# PCB-dol.net
KiCad netlist of a schematic drawn in EAGLE
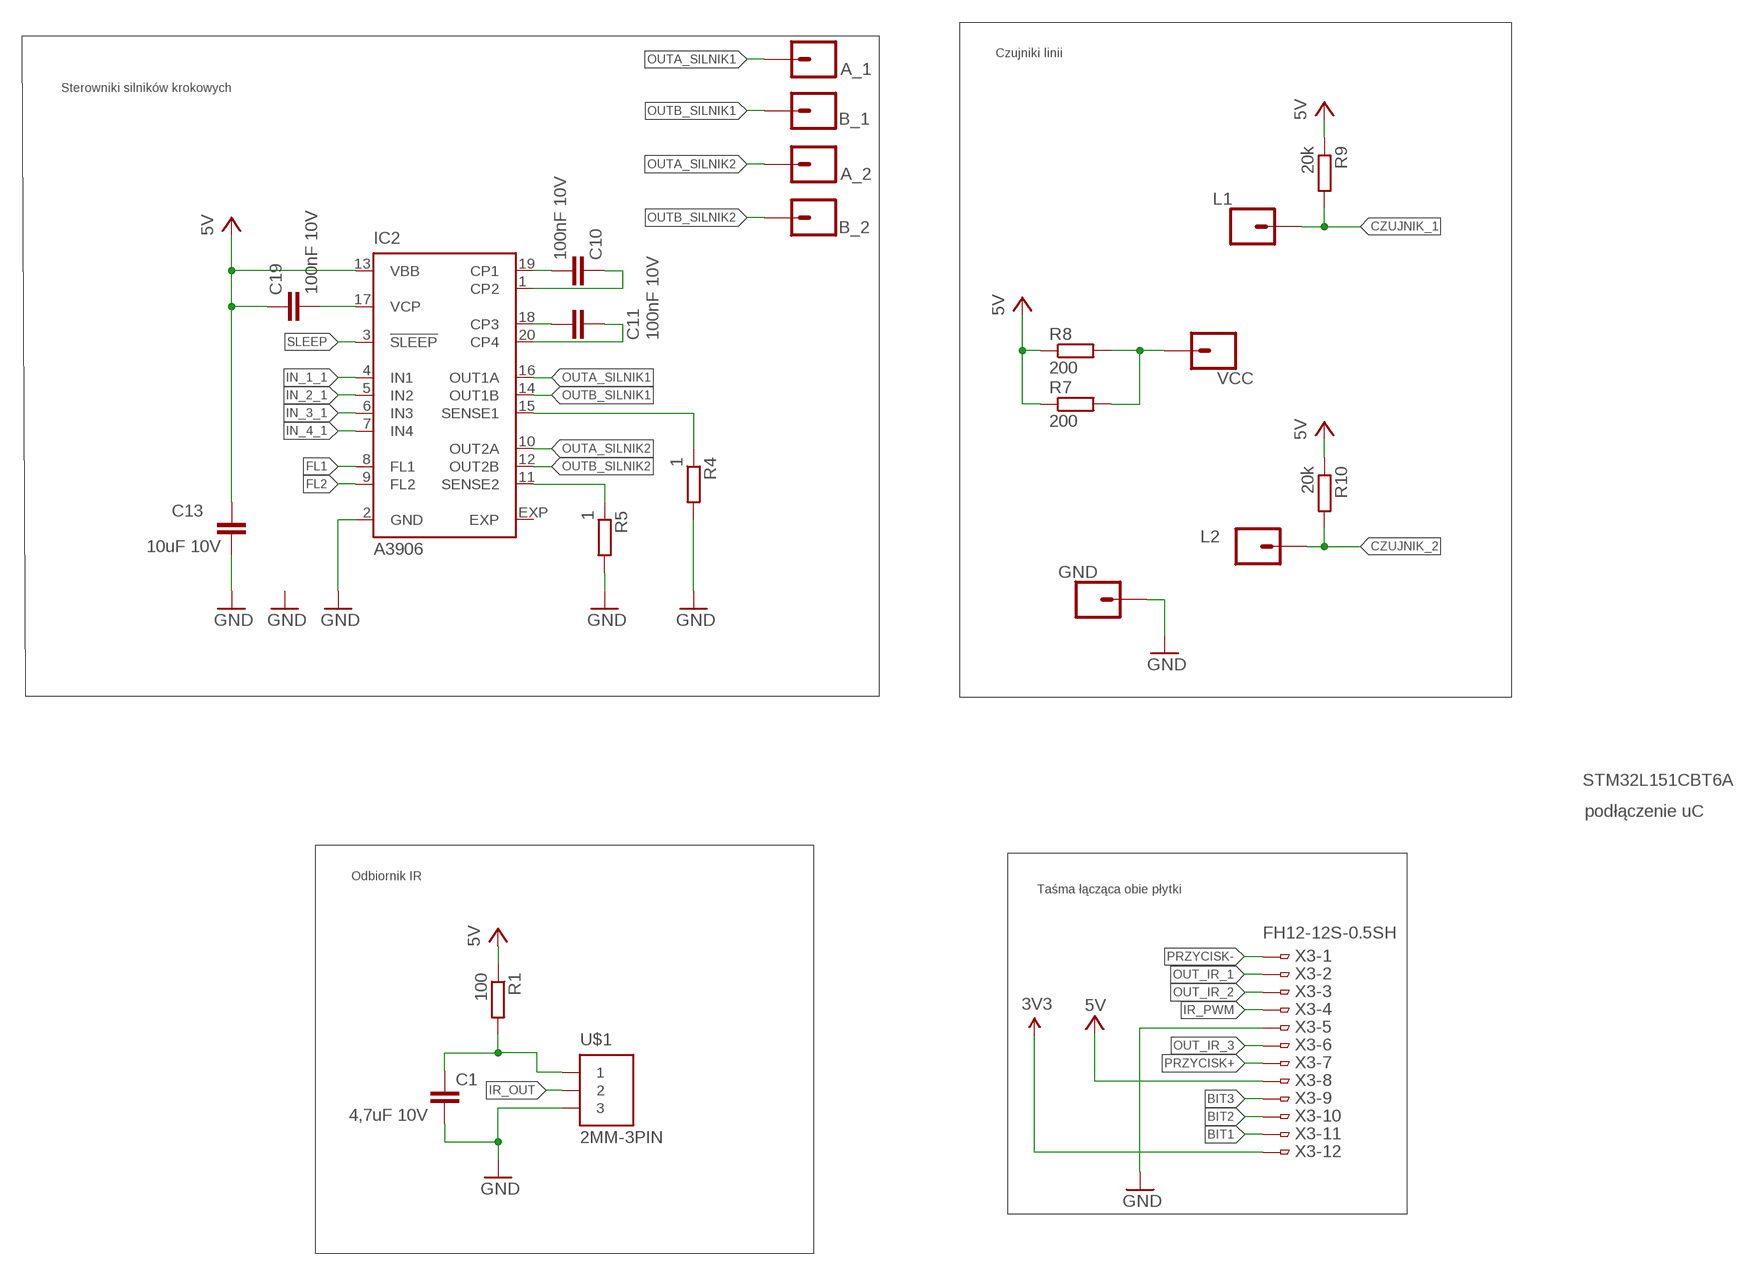
[diagram p0: schematic, sheet 1, part 1 of 2]
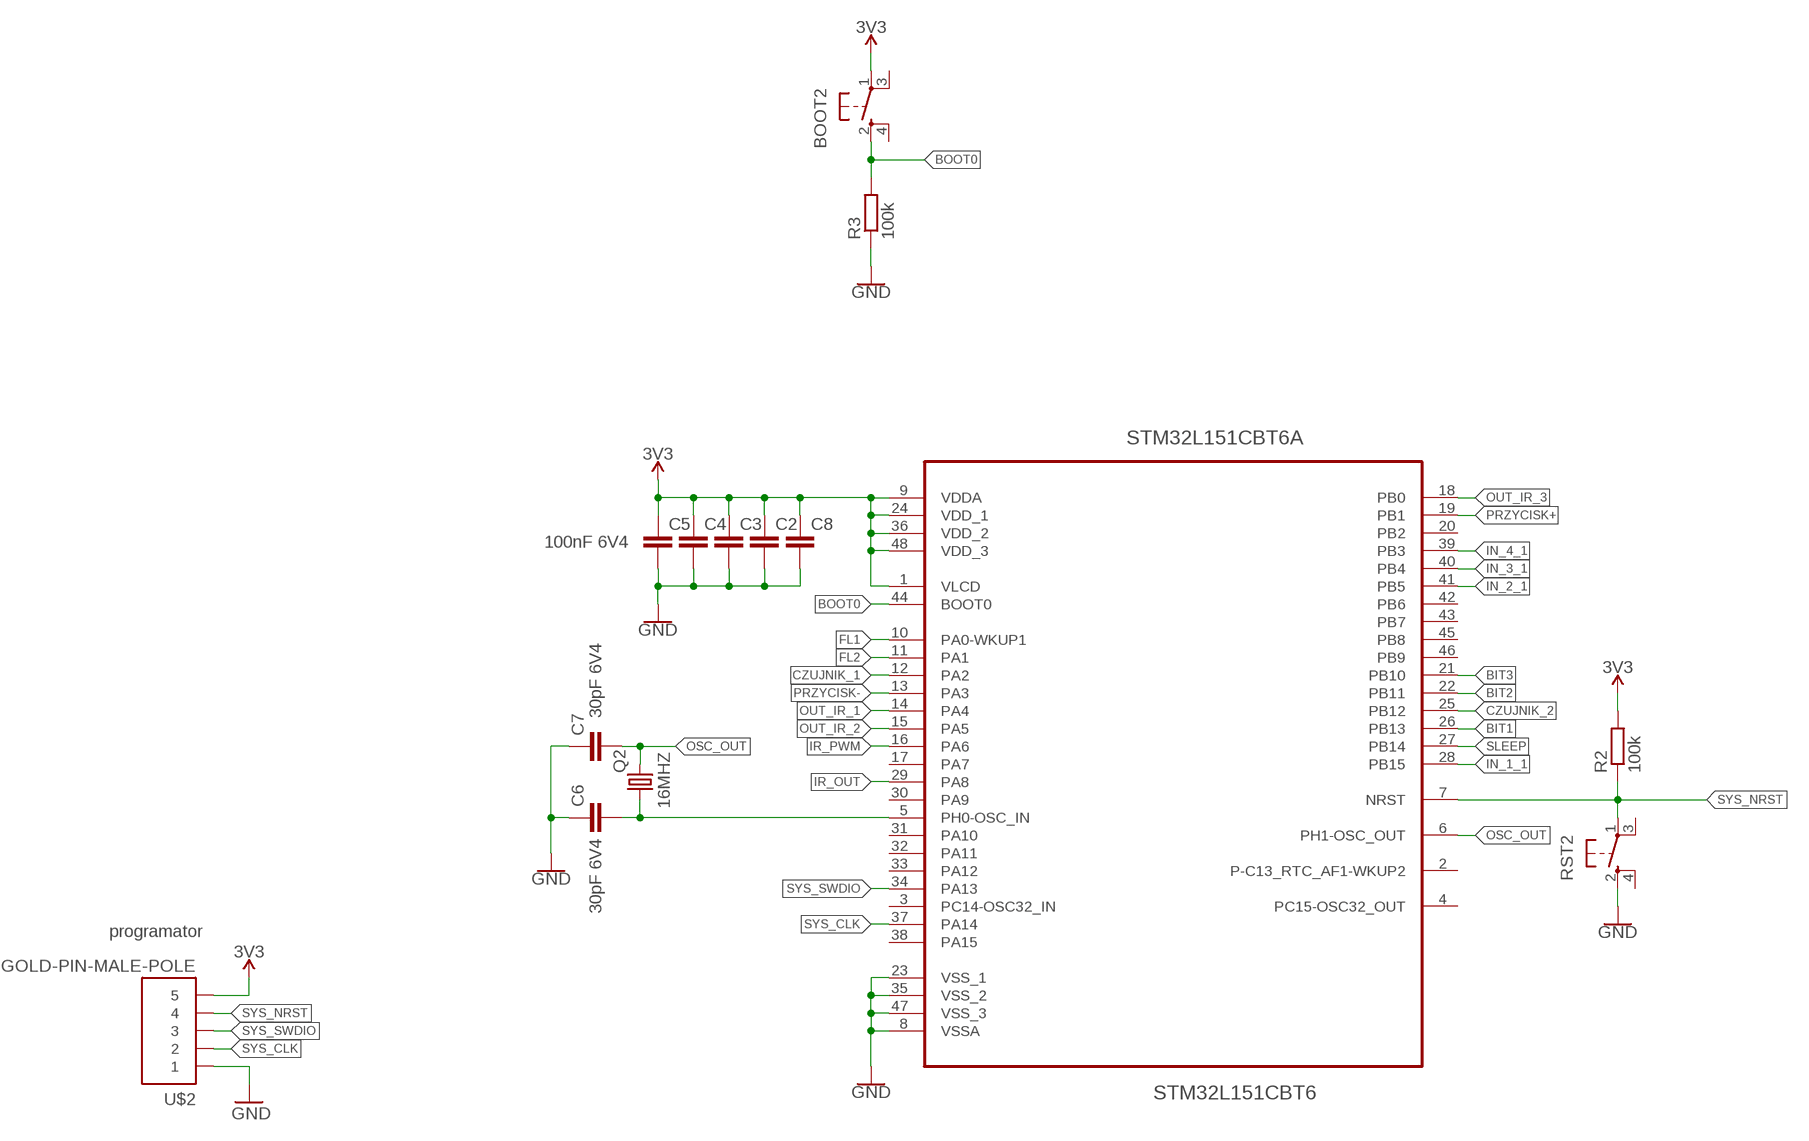
[diagram p1: schematic, sheet 1, part 2 of 2]

(export (version "E")
  (design (tool "Eeschema 10.0.6"))
  (components
    (comp (ref "A_1")
      (value "CONN_01PTH_NO_SILK_KIT")
      (footprint "eagle-import:1X01NS_KIT")
      (libsource (lib "eagle-import") (part "CONN_01PTH_NO_SILK_KIT"))
    )
    (comp (ref "A_2")
      (value "CONN_01PTH_NO_SILK_KIT")
      (footprint "eagle-import:1X01NS_KIT")
      (libsource (lib "eagle-import") (part "CONN_01PTH_NO_SILK_KIT"))
    )
    (comp (ref "BOOT2")
      (value "SPST_TACT-KMR2")
      (footprint "eagle-import:KMR2")
      (libsource (lib "eagle-import") (part "SPST_TACT-KMR2"))
    )
    (comp (ref "B_1")
      (value "CONN_01PTH_NO_SILK_KIT")
      (footprint "eagle-import:1X01NS_KIT")
      (libsource (lib "eagle-import") (part "CONN_01PTH_NO_SILK_KIT"))
    )
    (comp (ref "B_2")
      (value "CONN_01PTH_NO_SILK_KIT")
      (footprint "eagle-import:1X01NS_KIT")
      (libsource (lib "eagle-import") (part "CONN_01PTH_NO_SILK_KIT"))
    )
    (comp (ref "C1")
      (value "4,7uF 10V")
      (footprint "eagle-import:C0402")
      (libsource (lib "eagle-import") (part "C-EUC0402"))
    )
    (comp (ref "C2")
      (value "100nF 6V4")
      (footprint "eagle-import:C0402")
      (libsource (lib "eagle-import") (part "C-EUC0402"))
    )
    (comp (ref "C3")
      (value "100nF 6V4")
      (footprint "eagle-import:C0402")
      (libsource (lib "eagle-import") (part "C-EUC0402"))
    )
    (comp (ref "C4")
      (value "100nF 6V4")
      (footprint "eagle-import:C0402")
      (libsource (lib "eagle-import") (part "C-EUC0402"))
    )
    (comp (ref "C5")
      (value "100nF 6V4")
      (footprint "eagle-import:C0402")
      (libsource (lib "eagle-import") (part "C-EUC0402"))
    )
    (comp (ref "C6")
      (value "30pF 6V4")
      (footprint "eagle-import:C0402")
      (libsource (lib "eagle-import") (part "C-EUC0402"))
    )
    (comp (ref "C7")
      (value "30pF 6V4")
      (footprint "eagle-import:C0402")
      (libsource (lib "eagle-import") (part "C-EUC0402"))
    )
    (comp (ref "C8")
      (value "100nF 6V4")
      (footprint "eagle-import:C0402")
      (libsource (lib "eagle-import") (part "C-EUC0402"))
    )
    (comp (ref "C10")
      (value "100nF 10V")
      (footprint "eagle-import:C0402")
      (libsource (lib "eagle-import") (part "C-EUC0402"))
    )
    (comp (ref "C11")
      (value "100nF 10V")
      (footprint "eagle-import:C0402")
      (libsource (lib "eagle-import") (part "C-EUC0402"))
    )
    (comp (ref "C13")
      (value "10uF 10V")
      (footprint "eagle-import:C0402")
      (libsource (lib "eagle-import") (part "C-EUC0402"))
    )
    (comp (ref "C19")
      (value "100nF 10V")
      (footprint "eagle-import:C0402")
      (libsource (lib "eagle-import") (part "C-EUC0402"))
    )
    (comp (ref "GND")
      (value "CONN_01PTH_NO_SILK_KIT")
      (footprint "eagle-import:1X01NS_KIT")
      (libsource (lib "eagle-import") (part "CONN_01PTH_NO_SILK_KIT"))
    )
    (comp (ref "IC2")
      (value "A3906")
      (footprint "eagle-import:QFN20")
      (libsource (lib "eagle-import") (part "A3906"))
    )
    (comp (ref "L1")
      (value "CONN_01PTH_NO_SILK_KIT")
      (footprint "eagle-import:1X01NS_KIT")
      (libsource (lib "eagle-import") (part "CONN_01PTH_NO_SILK_KIT"))
    )
    (comp (ref "L2")
      (value "CONN_01PTH_NO_SILK_KIT")
      (footprint "eagle-import:1X01NS_KIT")
      (libsource (lib "eagle-import") (part "CONN_01PTH_NO_SILK_KIT"))
    )
    (comp (ref "Q2")
      (value "16MHZ")
      (footprint "eagle-import:3.2X2.5_KX-7")
      (libsource (lib "eagle-import") (part "KX-7"))
    )
    (comp (ref "R1")
      (value "100")
      (footprint "eagle-import:R0402")
      (libsource (lib "eagle-import") (part "R-EU_R0402"))
    )
    (comp (ref "R2")
      (value "100k")
      (footprint "eagle-import:R0402")
      (libsource (lib "eagle-import") (part "R-EU_R0402"))
    )
    (comp (ref "R3")
      (value "100k")
      (footprint "eagle-import:R0402")
      (libsource (lib "eagle-import") (part "R-EU_R0402"))
    )
    (comp (ref "R4")
      (value "1")
      (footprint "eagle-import:R0402")
      (libsource (lib "eagle-import") (part "R-EU_R0402"))
    )
    (comp (ref "R5")
      (value "1")
      (footprint "eagle-import:R0402")
      (libsource (lib "eagle-import") (part "R-EU_R0402"))
    )
    (comp (ref "R7")
      (value "200")
      (footprint "eagle-import:R0805")
      (libsource (lib "eagle-import") (part "R-EU_R0805"))
    )
    (comp (ref "R8")
      (value "200")
      (footprint "eagle-import:R0805")
      (libsource (lib "eagle-import") (part "R-EU_R0805"))
    )
    (comp (ref "R9")
      (value "20k")
      (footprint "eagle-import:R0402")
      (libsource (lib "eagle-import") (part "R-EU_R0402"))
    )
    (comp (ref "R10")
      (value "20k")
      (footprint "eagle-import:R0402")
      (libsource (lib "eagle-import") (part "R-EU_R0402"))
    )
    (comp (ref "RST2")
      (value "SPST_TACT-KMR2")
      (footprint "eagle-import:KMR2")
      (libsource (lib "eagle-import") (part "SPST_TACT-KMR2"))
    )
    (comp (ref "STM32L151CBT6A")
      (value "STM32L151CBT6")
      (footprint "eagle-import:QFP50P900X900X160-48N")
      (libsource (lib "eagle-import") (part "STM32L151CBT6"))
    )
    (comp (ref "U$1")
      (value "2MM-3PIN")
      (footprint "eagle-import:2MM-3PIN")
      (libsource (lib "eagle-import") (part "2MM-3PIN"))
    )
    (comp (ref "U$2")
      (value "GOLD-PIN-MALE-POLE")
      (footprint "eagle-import:PIN5")
      (libsource (lib "eagle-import") (part "GOLD-PIN-MALE-POLE"))
    )
    (comp (ref "VCC")
      (value "CONN_01PTH_NO_SILK_KIT")
      (footprint "eagle-import:1X01NS_KIT")
      (libsource (lib "eagle-import") (part "CONN_01PTH_NO_SILK_KIT"))
    )
    (comp (ref "X3")
      (value "FH12-12S-0.5SH")
      (footprint "eagle-import:FH12-12S-0.5SH")
      (fields (field (name "MPN") "FH12-12S-0.5SH(55)"))
      (libsource (lib "eagle-import") (part "FH12-12S-0.5SH"))
    )
  )
  (nets
    (net (code "1") (name "3V3") (class "Default")
      (node (ref "BOOT2") (pin "1") (pinfunction "P_1") (pintype "passive"))
      (node (ref "C2") (pin "1") (pinfunction "1_1") (pintype "passive"))
      (node (ref "C3") (pin "1") (pinfunction "1_1") (pintype "passive"))
      (node (ref "C4") (pin "1") (pinfunction "1_1") (pintype "passive"))
      (node (ref "C5") (pin "1") (pinfunction "1_1") (pintype "passive"))
      (node (ref "C8") (pin "1") (pinfunction "1_1") (pintype "passive"))
      (node (ref "R2") (pin "2") (pinfunction "2_2") (pintype "passive"))
      (node (ref "STM32L151CBT6A") (pin "1") (pinfunction "VLCD_1") (pintype "power_in"))
      (node (ref "STM32L151CBT6A") (pin "24") (pinfunction "VDD_1_24") (pintype "power_in"))
      (node (ref "STM32L151CBT6A") (pin "36") (pinfunction "VDD_2_36") (pintype "power_in"))
      (node (ref "STM32L151CBT6A") (pin "48") (pinfunction "VDD_3_48") (pintype "power_in"))
      (node (ref "STM32L151CBT6A") (pin "9") (pinfunction "VDDA_9") (pintype "power_in"))
      (node (ref "U$2") (pin "P$5") (pinfunction "5_P$5") (pintype "input"))
      (node (ref "X3") (pin "12") (pinfunction "1_12") (pintype "passive"))
    )
    (net (code "2") (name "5V") (class "Default")
      (node (ref "C13") (pin "2") (pinfunction "2_2") (pintype "passive"))
      (node (ref "C19") (pin "2") (pinfunction "2_2") (pintype "passive"))
      (node (ref "IC2") (pin "13") (pinfunction "VBB_13") (pintype "power_in"))
      (node (ref "R1") (pin "1") (pinfunction "1_1") (pintype "passive"))
      (node (ref "R10") (pin "1") (pinfunction "1_1") (pintype "passive"))
      (node (ref "R7") (pin "1") (pinfunction "1_1") (pintype "passive"))
      (node (ref "R8") (pin "1") (pinfunction "1_1") (pintype "passive"))
      (node (ref "R9") (pin "1") (pinfunction "1_1") (pintype "passive"))
      (node (ref "X3") (pin "8") (pinfunction "1_8") (pintype "passive"))
    )
    (net (code "3") (name "BIT1") (class "Default")
      (node (ref "STM32L151CBT6A") (pin "26") (pinfunction "PB13_26") (pintype "bidirectional"))
      (node (ref "X3") (pin "11") (pinfunction "1_11") (pintype "passive"))
    )
    (net (code "4") (name "BIT2") (class "Default")
      (node (ref "STM32L151CBT6A") (pin "22") (pinfunction "PB11_22") (pintype "bidirectional"))
      (node (ref "X3") (pin "10") (pinfunction "1_10") (pintype "passive"))
    )
    (net (code "5") (name "BIT3") (class "Default")
      (node (ref "STM32L151CBT6A") (pin "21") (pinfunction "PB10_21") (pintype "bidirectional"))
      (node (ref "X3") (pin "9") (pinfunction "1_9") (pintype "passive"))
    )
    (net (code "6") (name "BOOT0") (class "Default")
      (node (ref "BOOT2") (pin "2") (pinfunction "S_2") (pintype "passive"))
      (node (ref "R3") (pin "2") (pinfunction "2_2") (pintype "passive"))
      (node (ref "STM32L151CBT6A") (pin "44") (pinfunction "BOOT0_44") (pintype "input"))
    )
    (net (code "7") (name "CZUJNIK_1") (class "Default")
      (node (ref "L1") (pin "1") (pinfunction "1_1") (pintype "passive"))
      (node (ref "R9") (pin "2") (pinfunction "2_2") (pintype "passive"))
      (node (ref "STM32L151CBT6A") (pin "12") (pinfunction "PA2_12") (pintype "bidirectional"))
    )
    (net (code "8") (name "CZUJNIK_2") (class "Default")
      (node (ref "L2") (pin "1") (pinfunction "1_1") (pintype "passive"))
      (node (ref "R10") (pin "2") (pinfunction "2_2") (pintype "passive"))
      (node (ref "STM32L151CBT6A") (pin "25") (pinfunction "PB12_25") (pintype "bidirectional"))
    )
    (net (code "9") (name "FL1") (class "Default")
      (node (ref "IC2") (pin "8") (pinfunction "FL1_8") (pintype "input"))
      (node (ref "STM32L151CBT6A") (pin "10") (pinfunction "PA0-WKUP1_10") (pintype "bidirectional"))
    )
    (net (code "10") (name "FL2") (class "Default")
      (node (ref "IC2") (pin "9") (pinfunction "FL2_9") (pintype "input"))
      (node (ref "STM32L151CBT6A") (pin "11") (pinfunction "PA1_11") (pintype "bidirectional"))
    )
    (net (code "11") (name "GND") (class "Default")
      (node (ref "C1") (pin "2") (pinfunction "2_2") (pintype "passive"))
      (node (ref "C13") (pin "1") (pinfunction "1_1") (pintype "passive"))
      (node (ref "C2") (pin "2") (pinfunction "2_2") (pintype "passive"))
      (node (ref "C3") (pin "2") (pinfunction "2_2") (pintype "passive"))
      (node (ref "C4") (pin "2") (pinfunction "2_2") (pintype "passive"))
      (node (ref "C5") (pin "2") (pinfunction "2_2") (pintype "passive"))
      (node (ref "C6") (pin "1") (pinfunction "1_1") (pintype "passive"))
      (node (ref "C7") (pin "1") (pinfunction "1_1") (pintype "passive"))
      (node (ref "C8") (pin "2") (pinfunction "2_2") (pintype "passive"))
      (node (ref "GND") (pin "1") (pinfunction "1_1") (pintype "passive"))
      (node (ref "IC2") (pin "2") (pinfunction "GND_2") (pintype "power_in"))
      (node (ref "R3") (pin "1") (pinfunction "1_1") (pintype "passive"))
      (node (ref "R4") (pin "2") (pinfunction "2_2") (pintype "passive"))
      (node (ref "R5") (pin "2") (pinfunction "2_2") (pintype "passive"))
      (node (ref "RST2") (pin "2") (pinfunction "S_2") (pintype "passive"))
      (node (ref "STM32L151CBT6A") (pin "23") (pinfunction "VSS_1_23") (pintype "power_in"))
      (node (ref "STM32L151CBT6A") (pin "35") (pinfunction "VSS_2_35") (pintype "power_in"))
      (node (ref "STM32L151CBT6A") (pin "47") (pinfunction "VSS_3_47") (pintype "power_in"))
      (node (ref "STM32L151CBT6A") (pin "8") (pinfunction "VSSA_8") (pintype "power_in"))
      (node (ref "U$1") (pin "P$3") (pinfunction "3_P$3") (pintype "input"))
      (node (ref "U$2") (pin "P$1") (pinfunction "1_P$1") (pintype "input"))
      (node (ref "X3") (pin "5") (pinfunction "1_5") (pintype "passive"))
    )
    (net (code "12") (name "IN_1_1") (class "Default")
      (node (ref "IC2") (pin "4") (pinfunction "IN1_4") (pintype "input"))
      (node (ref "STM32L151CBT6A") (pin "28") (pinfunction "PB15_28") (pintype "bidirectional"))
    )
    (net (code "13") (name "IN_2_1") (class "Default")
      (node (ref "IC2") (pin "5") (pinfunction "IN2_5") (pintype "input"))
      (node (ref "STM32L151CBT6A") (pin "41") (pinfunction "PB5_41") (pintype "bidirectional"))
    )
    (net (code "14") (name "IN_3_1") (class "Default")
      (node (ref "IC2") (pin "6") (pinfunction "IN3_6") (pintype "input"))
      (node (ref "STM32L151CBT6A") (pin "40") (pinfunction "PB4_40") (pintype "bidirectional"))
    )
    (net (code "15") (name "IN_4_1") (class "Default")
      (node (ref "IC2") (pin "7") (pinfunction "IN4_7") (pintype "input"))
      (node (ref "STM32L151CBT6A") (pin "39") (pinfunction "PB3_39") (pintype "bidirectional"))
    )
    (net (code "16") (name "IR_OUT") (class "Default")
      (node (ref "STM32L151CBT6A") (pin "29") (pinfunction "PA8_29") (pintype "bidirectional"))
      (node (ref "U$1") (pin "P$2") (pinfunction "2_P$2") (pintype "input"))
    )
    (net (code "17") (name "IR_PWM") (class "Default")
      (node (ref "STM32L151CBT6A") (pin "16") (pinfunction "PA6_16") (pintype "bidirectional"))
      (node (ref "X3") (pin "4") (pinfunction "1_4") (pintype "passive"))
    )
    (net (code "18") (name "Net-(IC2-CP1)") (class "Default")
      (node (ref "C10") (pin "1") (pinfunction "1_1") (pintype "passive"))
      (node (ref "IC2") (pin "19") (pinfunction "CP1_19") (pintype "passive"))
    )
    (net (code "19") (name "Net-(IC2-CP2)") (class "Default")
      (node (ref "C10") (pin "2") (pinfunction "2_2") (pintype "passive"))
      (node (ref "IC2") (pin "1") (pinfunction "CP2_1") (pintype "passive"))
    )
    (net (code "20") (name "Net-(IC2-CP3)") (class "Default")
      (node (ref "C11") (pin "1") (pinfunction "1_1") (pintype "passive"))
      (node (ref "IC2") (pin "18") (pinfunction "CP3_18") (pintype "passive"))
    )
    (net (code "21") (name "Net-(IC2-CP4)") (class "Default")
      (node (ref "C11") (pin "2") (pinfunction "2_2") (pintype "passive"))
      (node (ref "IC2") (pin "20") (pinfunction "CP4_20") (pintype "passive"))
    )
    (net (code "22") (name "Net-(IC2-SENSE1)") (class "Default")
      (node (ref "IC2") (pin "15") (pinfunction "SENSE1_15") (pintype "input"))
      (node (ref "R4") (pin "1") (pinfunction "1_1") (pintype "passive"))
    )
    (net (code "23") (name "Net-(IC2-SENSE2)") (class "Default")
      (node (ref "IC2") (pin "11") (pinfunction "SENSE2_11") (pintype "input"))
      (node (ref "R5") (pin "1") (pinfunction "1_1") (pintype "passive"))
    )
    (net (code "24") (name "Net-(IC2-VCP)") (class "Default")
      (node (ref "C19") (pin "1") (pinfunction "1_1") (pintype "passive"))
      (node (ref "IC2") (pin "17") (pinfunction "VCP_17") (pintype "passive"))
    )
    (net (code "25") (name "Net-(R7-Pad2)") (class "Default")
      (node (ref "R7") (pin "2") (pinfunction "2_2") (pintype "passive"))
      (node (ref "R8") (pin "2") (pinfunction "2_2") (pintype "passive"))
      (node (ref "VCC") (pin "1") (pinfunction "1_1") (pintype "passive"))
    )
    (net (code "26") (name "Net-(STM32L151CBT6A-PH0-OSC_IN)") (class "Default")
      (node (ref "C6") (pin "2") (pinfunction "2_2") (pintype "passive"))
      (node (ref "Q2") (pin "1") (pinfunction "1_1") (pintype "passive"))
      (node (ref "STM32L151CBT6A") (pin "5") (pinfunction "PH0-OSC_IN_5") (pintype "input"))
    )
    (net (code "27") (name "Net-(U$1-1)") (class "Default")
      (node (ref "C1") (pin "1") (pinfunction "1_1") (pintype "passive"))
      (node (ref "R1") (pin "2") (pinfunction "2_2") (pintype "passive"))
      (node (ref "U$1") (pin "P$1") (pinfunction "1_P$1") (pintype "input"))
    )
    (net (code "28") (name "OSC_OUT") (class "Default")
      (node (ref "C7") (pin "2") (pinfunction "2_2") (pintype "passive"))
      (node (ref "Q2") (pin "3") (pinfunction "2_3") (pintype "passive"))
      (node (ref "STM32L151CBT6A") (pin "6") (pinfunction "PH1-OSC_OUT_6") (pintype "output"))
    )
    (net (code "29") (name "OUTA_SILNIK1") (class "Default")
      (node (ref "A_1") (pin "1") (pinfunction "1_1") (pintype "passive"))
      (node (ref "IC2") (pin "16") (pinfunction "OUT1A_16") (pintype "output"))
    )
    (net (code "30") (name "OUTA_SILNIK2") (class "Default")
      (node (ref "A_2") (pin "1") (pinfunction "1_1") (pintype "passive"))
      (node (ref "IC2") (pin "10") (pinfunction "OUT2A_10") (pintype "output"))
    )
    (net (code "31") (name "OUTB_SILNIK1") (class "Default")
      (node (ref "B_1") (pin "1") (pinfunction "1_1") (pintype "passive"))
      (node (ref "IC2") (pin "14") (pinfunction "OUT1B_14") (pintype "output"))
    )
    (net (code "32") (name "OUTB_SILNIK2") (class "Default")
      (node (ref "B_2") (pin "1") (pinfunction "1_1") (pintype "passive"))
      (node (ref "IC2") (pin "12") (pinfunction "OUT2B_12") (pintype "output"))
    )
    (net (code "33") (name "OUT_IR_1") (class "Default")
      (node (ref "STM32L151CBT6A") (pin "14") (pinfunction "PA4_14") (pintype "bidirectional"))
      (node (ref "X3") (pin "2") (pinfunction "1_2") (pintype "passive"))
    )
    (net (code "34") (name "OUT_IR_2") (class "Default")
      (node (ref "STM32L151CBT6A") (pin "15") (pinfunction "PA5_15") (pintype "bidirectional"))
      (node (ref "X3") (pin "3") (pinfunction "1_3") (pintype "passive"))
    )
    (net (code "35") (name "OUT_IR_3") (class "Default")
      (node (ref "STM32L151CBT6A") (pin "18") (pinfunction "PB0_18") (pintype "bidirectional"))
      (node (ref "X3") (pin "6") (pinfunction "1_6") (pintype "passive"))
    )
    (net (code "36") (name "PRZYCISK+") (class "Default")
      (node (ref "STM32L151CBT6A") (pin "19") (pinfunction "PB1_19") (pintype "bidirectional"))
      (node (ref "X3") (pin "7") (pinfunction "1_7") (pintype "passive"))
    )
    (net (code "37") (name "PRZYCISK-") (class "Default")
      (node (ref "STM32L151CBT6A") (pin "13") (pinfunction "PA3_13") (pintype "bidirectional"))
      (node (ref "X3") (pin "1") (pinfunction "1_1") (pintype "passive"))
    )
    (net (code "38") (name "SLEEP") (class "Default")
      (node (ref "IC2") (pin "3") (pinfunction "~{SLEEP}_3") (pintype "input"))
      (node (ref "STM32L151CBT6A") (pin "27") (pinfunction "PB14_27") (pintype "bidirectional"))
    )
    (net (code "39") (name "SYS_CLK") (class "Default")
      (node (ref "STM32L151CBT6A") (pin "37") (pinfunction "PA14_37") (pintype "bidirectional"))
      (node (ref "U$2") (pin "P$2") (pinfunction "2_P$2") (pintype "input"))
    )
    (net (code "40") (name "SYS_NRST") (class "Default")
      (node (ref "R2") (pin "1") (pinfunction "1_1") (pintype "passive"))
      (node (ref "RST2") (pin "1") (pinfunction "P_1") (pintype "passive"))
      (node (ref "STM32L151CBT6A") (pin "7") (pinfunction "NRST_7") (pintype "bidirectional"))
      (node (ref "U$2") (pin "P$4") (pinfunction "4_P$4") (pintype "input"))
    )
    (net (code "41") (name "SYS_SWDIO") (class "Default")
      (node (ref "STM32L151CBT6A") (pin "34") (pinfunction "PA13_34") (pintype "bidirectional"))
      (node (ref "U$2") (pin "P$3") (pinfunction "3_P$3") (pintype "input"))
    )
    (net (code "42") (name "unconnected-(BOOT2-P1-Pad3)") (class "Default")
      (node (ref "BOOT2") (pin "3") (pinfunction "P1_3") (pintype "passive"))
    )
    (net (code "43") (name "unconnected-(BOOT2-S1-Pad4)") (class "Default")
      (node (ref "BOOT2") (pin "4") (pinfunction "S1_4") (pintype "passive"))
    )
    (net (code "44") (name "unconnected-(IC2-PadEXP)") (class "Default")
      (node (ref "IC2") (pin "EXP") (pinfunction "EXP_EXP") (pintype "passive"))
    )
    (net (code "45") (name "unconnected-(RST2-P1-Pad3)") (class "Default")
      (node (ref "RST2") (pin "3") (pinfunction "P1_3") (pintype "passive"))
    )
    (net (code "46") (name "unconnected-(RST2-S1-Pad4)") (class "Default")
      (node (ref "RST2") (pin "4") (pinfunction "S1_4") (pintype "passive"))
    )
    (net (code "47") (name "unconnected-(STM32L151CBT6A-P-C13_RTC_AF1-WKUP2-Pad2)") (class "Default")
      (node (ref "STM32L151CBT6A") (pin "2") (pinfunction "P-C13_RTC_AF1-WKUP2_2") (pintype "bidirectional"))
    )
    (net (code "48") (name "unconnected-(STM32L151CBT6A-PA7-Pad17)") (class "Default")
      (node (ref "STM32L151CBT6A") (pin "17") (pinfunction "PA7_17") (pintype "bidirectional"))
    )
    (net (code "49") (name "unconnected-(STM32L151CBT6A-PA9-Pad30)") (class "Default")
      (node (ref "STM32L151CBT6A") (pin "30") (pinfunction "PA9_30") (pintype "bidirectional"))
    )
    (net (code "50") (name "unconnected-(STM32L151CBT6A-PA10-Pad31)") (class "Default")
      (node (ref "STM32L151CBT6A") (pin "31") (pinfunction "PA10_31") (pintype "bidirectional"))
    )
    (net (code "51") (name "unconnected-(STM32L151CBT6A-PA11-Pad32)") (class "Default")
      (node (ref "STM32L151CBT6A") (pin "32") (pinfunction "PA11_32") (pintype "bidirectional"))
    )
    (net (code "52") (name "unconnected-(STM32L151CBT6A-PA12-Pad33)") (class "Default")
      (node (ref "STM32L151CBT6A") (pin "33") (pinfunction "PA12_33") (pintype "bidirectional"))
    )
    (net (code "53") (name "unconnected-(STM32L151CBT6A-PA15-Pad38)") (class "Default")
      (node (ref "STM32L151CBT6A") (pin "38") (pinfunction "PA15_38") (pintype "bidirectional"))
    )
    (net (code "54") (name "unconnected-(STM32L151CBT6A-PB2-Pad20)") (class "Default")
      (node (ref "STM32L151CBT6A") (pin "20") (pinfunction "PB2_20") (pintype "bidirectional"))
    )
    (net (code "55") (name "unconnected-(STM32L151CBT6A-PB6-Pad42)") (class "Default")
      (node (ref "STM32L151CBT6A") (pin "42") (pinfunction "PB6_42") (pintype "bidirectional"))
    )
    (net (code "56") (name "unconnected-(STM32L151CBT6A-PB7-Pad43)") (class "Default")
      (node (ref "STM32L151CBT6A") (pin "43") (pinfunction "PB7_43") (pintype "bidirectional"))
    )
    (net (code "57") (name "unconnected-(STM32L151CBT6A-PB8-Pad45)") (class "Default")
      (node (ref "STM32L151CBT6A") (pin "45") (pinfunction "PB8_45") (pintype "bidirectional"))
    )
    (net (code "58") (name "unconnected-(STM32L151CBT6A-PB9-Pad46)") (class "Default")
      (node (ref "STM32L151CBT6A") (pin "46") (pinfunction "PB9_46") (pintype "bidirectional"))
    )
    (net (code "59") (name "unconnected-(STM32L151CBT6A-PC14-OSC32_IN-Pad3)") (class "Default")
      (node (ref "STM32L151CBT6A") (pin "3") (pinfunction "PC14-OSC32_IN_3") (pintype "input"))
    )
    (net (code "60") (name "unconnected-(STM32L151CBT6A-PC15-OSC32_OUT-Pad4)") (class "Default")
      (node (ref "STM32L151CBT6A") (pin "4") (pinfunction "PC15-OSC32_OUT_4") (pintype "output"))
    )
  )
)
